# AFC_senser_carrier_v3a.net
KiCad netlist of a schematic drawn in EAGLE
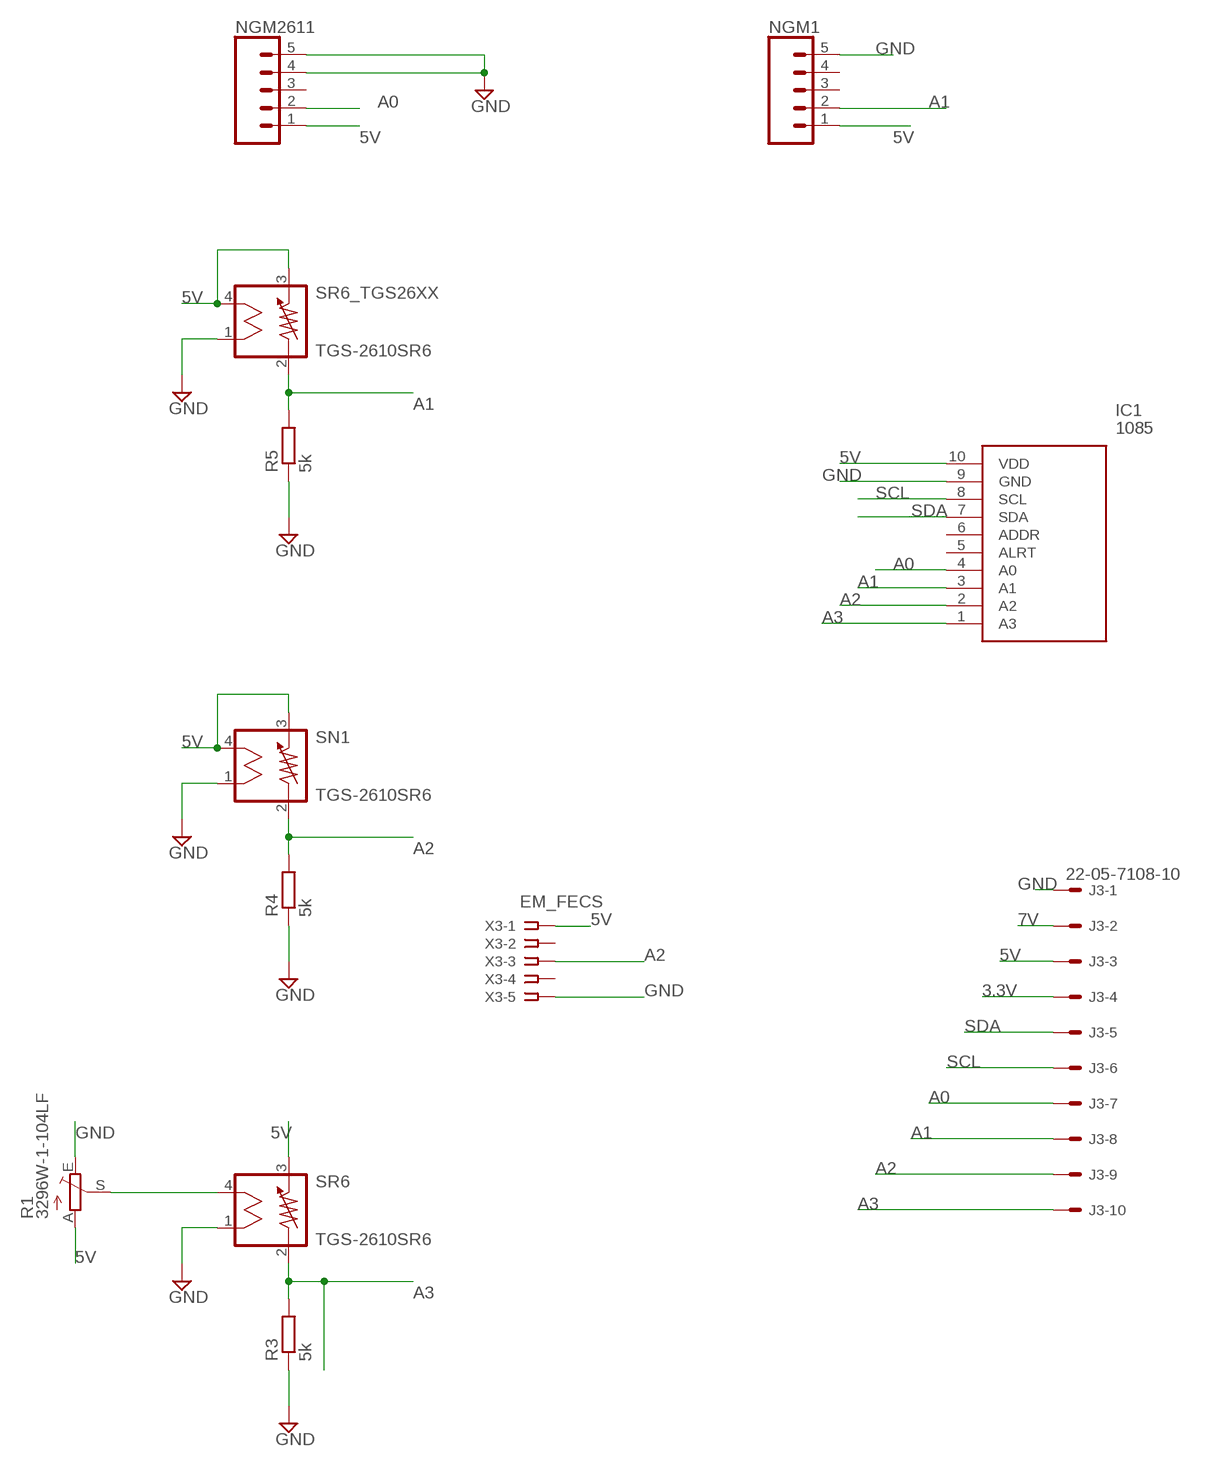
[diagram p0: schematic, sheet 2]
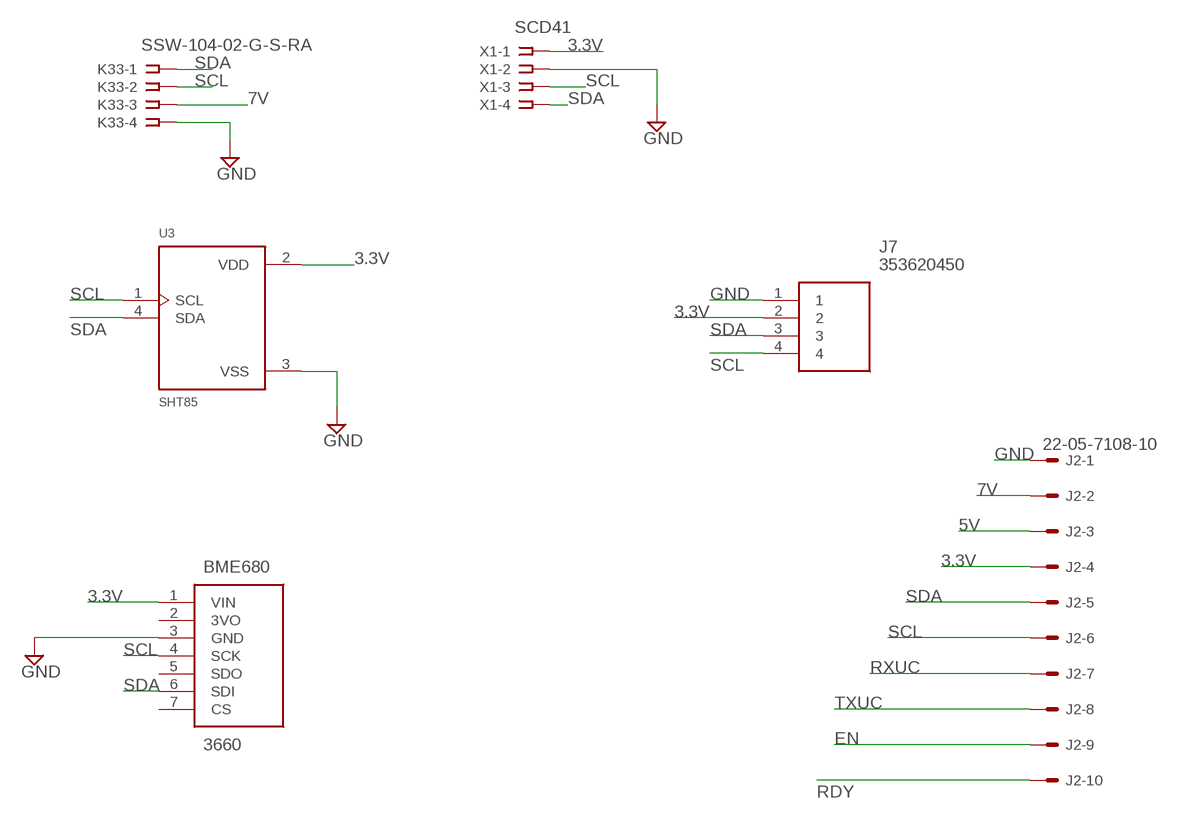
[diagram p1: schematic, sheet 3]
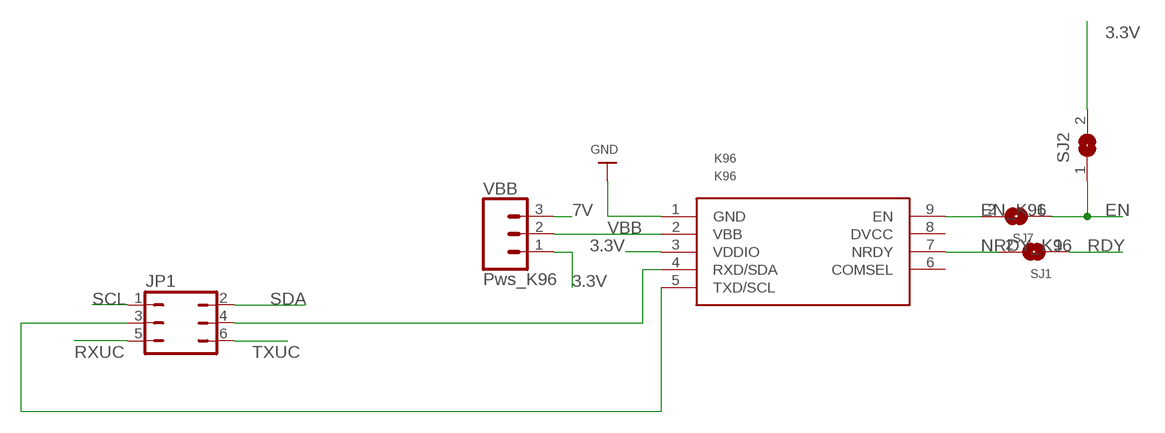
[diagram p2: schematic, sheet 4]

(export (version "E")
  (design (tool "Eeschema 10.0.6"))
  (components
    (comp (ref "IC1")
      (value "1085")
      (footprint "eagle-import:1085")
      (fields (field (name "MOUSER_PART_NUMBER") "485-1085"))
      (libsource (lib "eagle-import") (part "1085"))
    )
    (comp (ref "J3")
      (value "22-05-7108-10")
      (footprint "eagle-import:7395-10")
      (fields (field (name "MF") "MOLEX"))
      (libsource (lib "eagle-import") (part "22-?-1005-7108"))
    )
    (comp (ref "NGM1")
      (value "CONN_05LOCK")
      (footprint "eagle-import:1X05_LOCK")
      (libsource (lib "eagle-import") (part "CONN_05LOCK"))
    )
    (comp (ref "NGM2611")
      (value "CONN_05LOCK")
      (footprint "eagle-import:1X05_LOCK")
      (libsource (lib "eagle-import") (part "CONN_05LOCK"))
    )
    (comp (ref "R1")
      (value "3296W-1-104LF")
      (footprint "eagle-import:S64W")
      (libsource (lib "eagle-import") (part "TRIM_EU-S64W"))
    )
    (comp (ref "R3")
      (value "5k")
      (footprint "eagle-import:R0805")
      (libsource (lib "eagle-import") (part "R-EU_R0805"))
    )
    (comp (ref "R4")
      (value "5k")
      (footprint "eagle-import:R0805")
      (libsource (lib "eagle-import") (part "R-EU_R0805"))
    )
    (comp (ref "R5")
      (value "5k")
      (footprint "eagle-import:R0805")
      (libsource (lib "eagle-import") (part "R-EU_R0805"))
    )
    (comp (ref "SN1")
      (value "TGS-2610SR6")
      (footprint "eagle-import:SR6_TGS26XX")
      (libsource (lib "eagle-import") (part "TGS-2610SR6"))
    )
    (comp (ref "SR6")
      (value "TGS-2610SR6")
      (footprint "eagle-import:SR6_TGS26XX")
      (libsource (lib "eagle-import") (part "TGS-2610SR6"))
    )
    (comp (ref "SR6_TGS26XX")
      (value "TGS-2610SR6")
      (footprint "eagle-import:SR6_TGS26XX")
      (libsource (lib "eagle-import") (part "TGS-2610SR6"))
    )
    (comp (ref "X3")
      (value "EM_FECS")
      (footprint "eagle-import:SSW-105-02-G-S")
      (fields (field (name "MF") "Samtec Inc.") (field (name "MPN") "SSW-105-02-G-S"))
      (libsource (lib "eagle-import") (part "SSW-105-02-G-S"))
    )
    (comp (ref "BME680")
      (value "3660")
      (footprint "eagle-import:3660")
      (fields (field (name "MOUSER_PART_NUMBER") "485-3660"))
      (libsource (lib "eagle-import") (part "3660"))
    )
    (comp (ref "J2")
      (value "22-05-7108-10")
      (footprint "eagle-import:7395-10")
      (fields (field (name "MF") "MOLEX"))
      (libsource (lib "eagle-import") (part "22-?-1005-7108"))
    )
    (comp (ref "J7")
      (value "353620450")
      (footprint "eagle-import:SHDR4W50P0X200_1X4_1030X550X85")
      (libsource (lib "eagle-import") (part "353620450"))
    )
    (comp (ref "K33")
      (value "SSW-104-02-G-S-RA")
      (footprint "eagle-import:SSW-104-02-G-S-RA")
      (fields (field (name "MF") "Samtec Inc."))
      (libsource (lib "eagle-import") (part "SSW-104-02-G-S-RA"))
    )
    (comp (ref "U3")
      (value "SHT85")
      (footprint "eagle-import:XDCR_SHT85")
      (fields (field (name "MF") "Sensirion AG"))
      (libsource (lib "eagle-import") (part "SHT85"))
    )
    (comp (ref "X1")
      (value "SCD41")
      (footprint "eagle-import:SSW-104-02-G-S")
      (fields (field (name "MF") "Samtec Inc.") (field (name "MPN") "SSW-104-02-G-S"))
      (libsource (lib "eagle-import") (part "SSW-104-02-G-S"))
    )
    (comp (ref "JP1")
      (value "JP3Q")
      (footprint "eagle-import:JP3Q")
      (libsource (lib "eagle-import") (part "JP3Q"))
    )
    (comp (ref "K96")
      (value "K96")
      (footprint "eagle-import:SENSEAIR_SUNRISE")
      (libsource (lib "eagle-import") (part "SENSEAIR_SUNRISESUNRISE"))
    )
    (comp (ref "SJ1")
      (value "SOLDERJUMPERCLOSED")
      (footprint "eagle-import:SOLDERJUMPER_CLOSEDWIRE")
      (libsource (lib "eagle-import") (part "SOLDERJUMPERCLOSED"))
    )
    (comp (ref "SJ2") (value "SJ") (footprint "eagle-import:SJ") (libsource (lib "eagle-import") (part "SJ")))
    (comp (ref "SJ7")
      (value "SOLDERJUMPERCLOSED")
      (footprint "eagle-import:SOLDERJUMPER_CLOSEDWIRE")
      (libsource (lib "eagle-import") (part "SOLDERJUMPERCLOSED"))
    )
    (comp (ref "VBB")
      (value "Pws_K96")
      (footprint "eagle-import:1X03")
      (libsource (lib "eagle-import") (part "CONN_03"))
    )
  )
  (nets
    (net (code "1") (name "3.3V") (class "Default")
      (node (ref "BME680") (pin "1") (pinfunction "VIN_1") (pintype "bidirectional"))
      (node (ref "J2") (pin "4") (pinfunction "S_4") (pintype "passive"))
      (node (ref "J3") (pin "4") (pinfunction "S_4") (pintype "passive"))
      (node (ref "J7") (pin "2") (pinfunction "2_2") (pintype "bidirectional"))
      (node (ref "K96") (pin "3") (pinfunction "VDDIO_3") (pintype "bidirectional"))
      (node (ref "SJ2") (pin "2") (pinfunction "2_2") (pintype "passive"))
      (node (ref "U3") (pin "2") (pinfunction "VDD_2") (pintype "power_in"))
      (node (ref "VBB") (pin "1") (pinfunction "1_1") (pintype "passive"))
      (node (ref "X1") (pin "1") (pinfunction "1_1") (pintype "passive"))
    )
    (net (code "2") (name "5V") (class "Default")
      (node (ref "IC1") (pin "10") (pinfunction "VDD_10") (pintype "bidirectional"))
      (node (ref "J2") (pin "3") (pinfunction "S_3") (pintype "passive"))
      (node (ref "J3") (pin "3") (pinfunction "S_3") (pintype "passive"))
      (node (ref "NGM1") (pin "1") (pinfunction "1_1") (pintype "passive"))
      (node (ref "NGM2611") (pin "1") (pinfunction "1_1") (pintype "passive"))
      (node (ref "R1") (pin "A") (pinfunction "A_A") (pintype "passive"))
      (node (ref "SN1") (pin "3") (pinfunction "3_3") (pintype "passive"))
      (node (ref "SN1") (pin "4") (pinfunction "4_4") (pintype "passive"))
      (node (ref "SR6") (pin "3") (pinfunction "3_3") (pintype "passive"))
      (node (ref "SR6_TGS26XX") (pin "3") (pinfunction "3_3") (pintype "passive"))
      (node (ref "SR6_TGS26XX") (pin "4") (pinfunction "4_4") (pintype "passive"))
      (node (ref "X3") (pin "1") (pinfunction "1_1") (pintype "passive"))
    )
    (net (code "3") (name "7V") (class "Default")
      (node (ref "J2") (pin "2") (pinfunction "S_2") (pintype "passive"))
      (node (ref "J3") (pin "2") (pinfunction "S_2") (pintype "passive"))
      (node (ref "K33") (pin "3") (pinfunction "1_3") (pintype "passive"))
      (node (ref "VBB") (pin "3") (pinfunction "3_3") (pintype "passive"))
    )
    (net (code "4") (name "A0") (class "Default")
      (node (ref "IC1") (pin "4") (pinfunction "A0_4") (pintype "bidirectional"))
      (node (ref "J3") (pin "7") (pinfunction "S_7") (pintype "passive"))
      (node (ref "NGM2611") (pin "2") (pinfunction "2_2") (pintype "passive"))
    )
    (net (code "5") (name "A1") (class "Default")
      (node (ref "IC1") (pin "3") (pinfunction "A1_3") (pintype "bidirectional"))
      (node (ref "J3") (pin "8") (pinfunction "S_8") (pintype "passive"))
      (node (ref "NGM1") (pin "2") (pinfunction "2_2") (pintype "passive"))
      (node (ref "R5") (pin "2") (pinfunction "2_2") (pintype "passive"))
      (node (ref "SR6_TGS26XX") (pin "2") (pinfunction "2_2") (pintype "passive"))
    )
    (net (code "6") (name "A2") (class "Default")
      (node (ref "IC1") (pin "2") (pinfunction "A2_2") (pintype "bidirectional"))
      (node (ref "J3") (pin "9") (pinfunction "S_9") (pintype "passive"))
      (node (ref "R4") (pin "2") (pinfunction "2_2") (pintype "passive"))
      (node (ref "SN1") (pin "2") (pinfunction "2_2") (pintype "passive"))
      (node (ref "X3") (pin "3") (pinfunction "1_3") (pintype "passive"))
    )
    (net (code "7") (name "A3") (class "Default")
      (node (ref "IC1") (pin "1") (pinfunction "A3_1") (pintype "bidirectional"))
      (node (ref "J3") (pin "10") (pinfunction "S_10") (pintype "passive"))
      (node (ref "R3") (pin "2") (pinfunction "2_2") (pintype "passive"))
      (node (ref "SR6") (pin "2") (pinfunction "2_2") (pintype "passive"))
    )
    (net (code "8") (name "EN") (class "Default")
      (node (ref "J2") (pin "9") (pinfunction "S_9") (pintype "passive"))
      (node (ref "SJ2") (pin "1") (pinfunction "1_1") (pintype "passive"))
      (node (ref "SJ7") (pin "1") (pinfunction "1_1") (pintype "passive"))
    )
    (net (code "9") (name "EN_K96") (class "Default")
      (node (ref "K96") (pin "9") (pinfunction "EN_9") (pintype "bidirectional"))
      (node (ref "SJ7") (pin "2") (pinfunction "2_2") (pintype "passive"))
    )
    (net (code "10") (name "GND") (class "Default")
      (node (ref "BME680") (pin "3") (pinfunction "GND_3") (pintype "bidirectional"))
      (node (ref "IC1") (pin "9") (pinfunction "GND_9") (pintype "bidirectional"))
      (node (ref "J2") (pin "1") (pinfunction "S_1") (pintype "passive"))
      (node (ref "J3") (pin "1") (pinfunction "S_1") (pintype "passive"))
      (node (ref "J7") (pin "1") (pinfunction "1_1") (pintype "bidirectional"))
      (node (ref "K33") (pin "4") (pinfunction "1_4") (pintype "passive"))
      (node (ref "K96") (pin "1") (pinfunction "GND_1") (pintype "power_in"))
      (node (ref "NGM1") (pin "5") (pinfunction "5_5") (pintype "passive"))
      (node (ref "NGM2611") (pin "4") (pinfunction "4_4") (pintype "passive"))
      (node (ref "NGM2611") (pin "5") (pinfunction "5_5") (pintype "passive"))
      (node (ref "R1") (pin "E") (pinfunction "E_E") (pintype "passive"))
      (node (ref "R3") (pin "1") (pinfunction "1_1") (pintype "passive"))
      (node (ref "R4") (pin "1") (pinfunction "1_1") (pintype "passive"))
      (node (ref "R5") (pin "1") (pinfunction "1_1") (pintype "passive"))
      (node (ref "SN1") (pin "1") (pinfunction "1_1") (pintype "passive"))
      (node (ref "SR6") (pin "1") (pinfunction "1_1") (pintype "passive"))
      (node (ref "SR6_TGS26XX") (pin "1") (pinfunction "1_1") (pintype "passive"))
      (node (ref "U3") (pin "3") (pinfunction "VSS_3") (pintype "power_in"))
      (node (ref "X1") (pin "2") (pinfunction "1_2") (pintype "passive"))
      (node (ref "X3") (pin "5") (pinfunction "1_5") (pintype "passive"))
    )
    (net (code "11") (name "NRDY_K96") (class "Default")
      (node (ref "K96") (pin "7") (pinfunction "NRDY_7") (pintype "output"))
      (node (ref "SJ1") (pin "2") (pinfunction "2_2") (pintype "passive"))
    )
    (net (code "12") (name "Net-(K96-RXD{slash}SDA)") (class "Default")
      (node (ref "JP1") (pin "4") (pinfunction "4_4") (pintype "passive"))
      (node (ref "K96") (pin "4") (pinfunction "RXD/SDA_4") (pintype "bidirectional"))
    )
    (net (code "13") (name "Net-(K96-TXD{slash}SCL)") (class "Default")
      (node (ref "JP1") (pin "3") (pinfunction "3_3") (pintype "passive"))
      (node (ref "K96") (pin "5") (pinfunction "TXD/SCL_5") (pintype "bidirectional"))
    )
    (net (code "14") (name "Net-(R1-PadS)") (class "Default")
      (node (ref "R1") (pin "S") (pinfunction "S_S") (pintype "passive"))
      (node (ref "SR6") (pin "4") (pinfunction "4_4") (pintype "passive"))
    )
    (net (code "15") (name "RDY") (class "Default")
      (node (ref "J2") (pin "10") (pinfunction "S_10") (pintype "passive"))
      (node (ref "SJ1") (pin "1") (pinfunction "1_1") (pintype "passive"))
    )
    (net (code "16") (name "RXUC") (class "Default")
      (node (ref "J2") (pin "7") (pinfunction "S_7") (pintype "passive"))
      (node (ref "JP1") (pin "5") (pinfunction "5_5") (pintype "passive"))
    )
    (net (code "17") (name "SCL") (class "Default")
      (node (ref "BME680") (pin "4") (pinfunction "SCK_4") (pintype "bidirectional"))
      (node (ref "IC1") (pin "8") (pinfunction "SCL_8") (pintype "bidirectional"))
      (node (ref "J2") (pin "6") (pinfunction "S_6") (pintype "passive"))
      (node (ref "J3") (pin "6") (pinfunction "S_6") (pintype "passive"))
      (node (ref "J7") (pin "4") (pinfunction "4_4") (pintype "bidirectional"))
      (node (ref "JP1") (pin "1") (pinfunction "1_1") (pintype "passive"))
      (node (ref "K33") (pin "2") (pinfunction "1_2") (pintype "passive"))
      (node (ref "U3") (pin "1") (pinfunction "SCL_1") (pintype "input"))
      (node (ref "X1") (pin "3") (pinfunction "1_3") (pintype "passive"))
    )
    (net (code "18") (name "SDA") (class "Default")
      (node (ref "BME680") (pin "6") (pinfunction "SDI_6") (pintype "bidirectional"))
      (node (ref "IC1") (pin "7") (pinfunction "SDA_7") (pintype "bidirectional"))
      (node (ref "J2") (pin "5") (pinfunction "S_5") (pintype "passive"))
      (node (ref "J3") (pin "5") (pinfunction "S_5") (pintype "passive"))
      (node (ref "J7") (pin "3") (pinfunction "3_3") (pintype "bidirectional"))
      (node (ref "JP1") (pin "2") (pinfunction "2_2") (pintype "passive"))
      (node (ref "K33") (pin "1") (pinfunction "1_1") (pintype "passive"))
      (node (ref "U3") (pin "4") (pinfunction "SDA_4") (pintype "bidirectional"))
      (node (ref "X1") (pin "4") (pinfunction "1_4") (pintype "passive"))
    )
    (net (code "19") (name "TXUC") (class "Default")
      (node (ref "J2") (pin "8") (pinfunction "S_8") (pintype "passive"))
      (node (ref "JP1") (pin "6") (pinfunction "6_6") (pintype "passive"))
    )
    (net (code "20") (name "VBB") (class "Default")
      (node (ref "K96") (pin "2") (pinfunction "VBB_2") (pintype "power_in"))
      (node (ref "VBB") (pin "2") (pinfunction "2_2") (pintype "passive"))
    )
    (net (code "21") (name "unconnected-(BME680-3VO-Pad2)") (class "Default")
      (node (ref "BME680") (pin "2") (pinfunction "3VO_2") (pintype "bidirectional"))
    )
    (net (code "22") (name "unconnected-(BME680-CS-Pad7)") (class "Default")
      (node (ref "BME680") (pin "7") (pinfunction "CS_7") (pintype "bidirectional"))
    )
    (net (code "23") (name "unconnected-(BME680-SDO-Pad5)") (class "Default")
      (node (ref "BME680") (pin "5") (pinfunction "SDO_5") (pintype "bidirectional"))
    )
    (net (code "24") (name "unconnected-(IC1-ADDR-Pad6)") (class "Default")
      (node (ref "IC1") (pin "6") (pinfunction "ADDR_6") (pintype "bidirectional"))
    )
    (net (code "25") (name "unconnected-(IC1-ALRT-Pad5)") (class "Default")
      (node (ref "IC1") (pin "5") (pinfunction "ALRT_5") (pintype "bidirectional"))
    )
    (net (code "26") (name "unconnected-(K96-COMSEL-Pad6)") (class "Default")
      (node (ref "K96") (pin "6") (pinfunction "COMSEL_6") (pintype "bidirectional"))
    )
    (net (code "27") (name "unconnected-(K96-DVCC-Pad8)") (class "Default")
      (node (ref "K96") (pin "8") (pinfunction "DVCC_8") (pintype "bidirectional"))
    )
    (net (code "28") (name "unconnected-(NGM1-Pad3)") (class "Default")
      (node (ref "NGM1") (pin "3") (pinfunction "3_3") (pintype "passive"))
    )
    (net (code "29") (name "unconnected-(NGM1-Pad4)") (class "Default")
      (node (ref "NGM1") (pin "4") (pinfunction "4_4") (pintype "passive"))
    )
    (net (code "30") (name "unconnected-(NGM2611-Pad3)") (class "Default")
      (node (ref "NGM2611") (pin "3") (pinfunction "3_3") (pintype "passive"))
    )
    (net (code "31") (name "unconnected-(X3B-1-Pad2)") (class "Default")
      (node (ref "X3") (pin "2") (pinfunction "1_2") (pintype "passive"))
    )
    (net (code "32") (name "unconnected-(X3D-1-Pad4)") (class "Default")
      (node (ref "X3") (pin "4") (pinfunction "1_4") (pintype "passive"))
    )
  )
)
